# relay.net
KiCad netlist of a schematic drawn in EAGLE
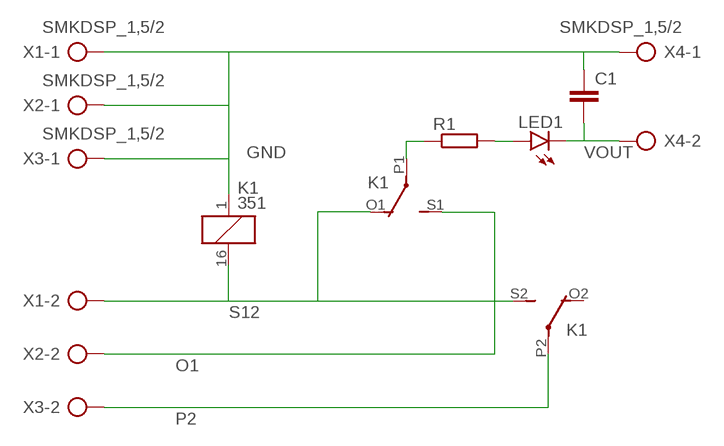
[diagram p0: schematic, sheet 1]

(export (version "E")
  (design (tool "Eeschema 10.0.6"))
  (components
    (comp (ref "C1")
      (value "C-EU025-025X050")
      (footprint "eagle-import:C025-025X050")
      (libsource (lib "eagle-import") (part "C-EU025-025X050"))
    )
    (comp (ref "K1")
      (value "351")
      (footprint "eagle-import:351")
      (libsource (lib "eagle-import") (part "351"))
    )
    (comp (ref "LED1")
      (value "LED3MM")
      (footprint "eagle-import:LED3MM")
      (libsource (lib "eagle-import") (part "LED3MM"))
    )
    (comp (ref "R1")
      (value "R-EU_0207/10")
      (footprint "eagle-import:0207_10")
      (libsource (lib "eagle-import") (part "R-EU_0207/10"))
    )
    (comp (ref "X1")
      (value "SMKDSP_1,5/2")
      (footprint "eagle-import:SMKDSP_1,5_2")
      (fields (field (name "MF") "FARNELL") (field (name "MPN") "1733570"))
      (libsource (lib "eagle-import") (part "SMKDSP_1,5/2"))
    )
    (comp (ref "X2")
      (value "SMKDSP_1,5/2")
      (footprint "eagle-import:SMKDSP_1,5_2")
      (fields (field (name "MF") "FARNELL") (field (name "MPN") "1733570"))
      (libsource (lib "eagle-import") (part "SMKDSP_1,5/2"))
    )
    (comp (ref "X3")
      (value "SMKDSP_1,5/2")
      (footprint "eagle-import:SMKDSP_1,5_2")
      (fields (field (name "MF") "FARNELL") (field (name "MPN") "1733570"))
      (libsource (lib "eagle-import") (part "SMKDSP_1,5/2"))
    )
    (comp (ref "X4")
      (value "SMKDSP_1,5/2")
      (footprint "eagle-import:SMKDSP_1,5_2")
      (fields (field (name "MF") "FARNELL") (field (name "MPN") "1733570"))
      (libsource (lib "eagle-import") (part "SMKDSP_1,5/2"))
    )
  )
  (nets
    (net (code "1") (name "/GND") (class "Default")
      (node (ref "C1") (pin "1") (pinfunction "1_1") (pintype "passive"))
      (node (ref "K1") (pin "1") (pinfunction "1_1") (pintype "passive"))
      (node (ref "X1") (pin "1") (pinfunction "KL_1") (pintype "passive"))
      (node (ref "X2") (pin "1") (pinfunction "KL_1") (pintype "passive"))
      (node (ref "X3") (pin "1") (pinfunction "KL_1") (pintype "passive"))
      (node (ref "X4") (pin "1") (pinfunction "KL_1") (pintype "passive"))
    )
    (net (code "2") (name "/O1") (class "Default")
      (node (ref "K1") (pin "S1") (pinfunction "S_S1") (pintype "passive"))
      (node (ref "X2") (pin "2") (pinfunction "KL_2") (pintype "passive"))
    )
    (net (code "3") (name "/P2") (class "Default")
      (node (ref "K1") (pin "P2") (pinfunction "P_P2") (pintype "passive"))
      (node (ref "X3") (pin "2") (pinfunction "KL_2") (pintype "passive"))
    )
    (net (code "4") (name "/S12") (class "Default")
      (node (ref "K1") (pin "16") (pinfunction "2_16") (pintype "passive"))
      (node (ref "K1") (pin "O1") (pinfunction "O_O1") (pintype "passive"))
      (node (ref "K1") (pin "S2") (pinfunction "S_S2") (pintype "passive"))
      (node (ref "X1") (pin "2") (pinfunction "KL_2") (pintype "passive"))
    )
    (net (code "5") (name "/VOUT") (class "Default")
      (node (ref "C1") (pin "2") (pinfunction "2_2") (pintype "passive"))
      (node (ref "LED1") (pin "K") (pinfunction "C_K") (pintype "passive"))
      (node (ref "X4") (pin "2") (pinfunction "KL_2") (pintype "passive"))
    )
    (net (code "6") (name "Net-(K1B-P)") (class "Default")
      (node (ref "K1") (pin "P1") (pinfunction "P_P1") (pintype "passive"))
      (node (ref "R1") (pin "1") (pinfunction "1_1") (pintype "passive"))
    )
    (net (code "7") (name "Net-(LED1-PadA)") (class "Default")
      (node (ref "LED1") (pin "A") (pinfunction "A_A") (pintype "passive"))
      (node (ref "R1") (pin "2") (pinfunction "2_2") (pintype "passive"))
    )
    (net (code "8") (name "unconnected-(K1C-O-PadO2)") (class "Default")
      (node (ref "K1") (pin "O2") (pinfunction "O_O2") (pintype "passive"))
    )
  )
)
